# Top_Sheet.net
KiCad netlist of a schematic drawn in Altium Designer
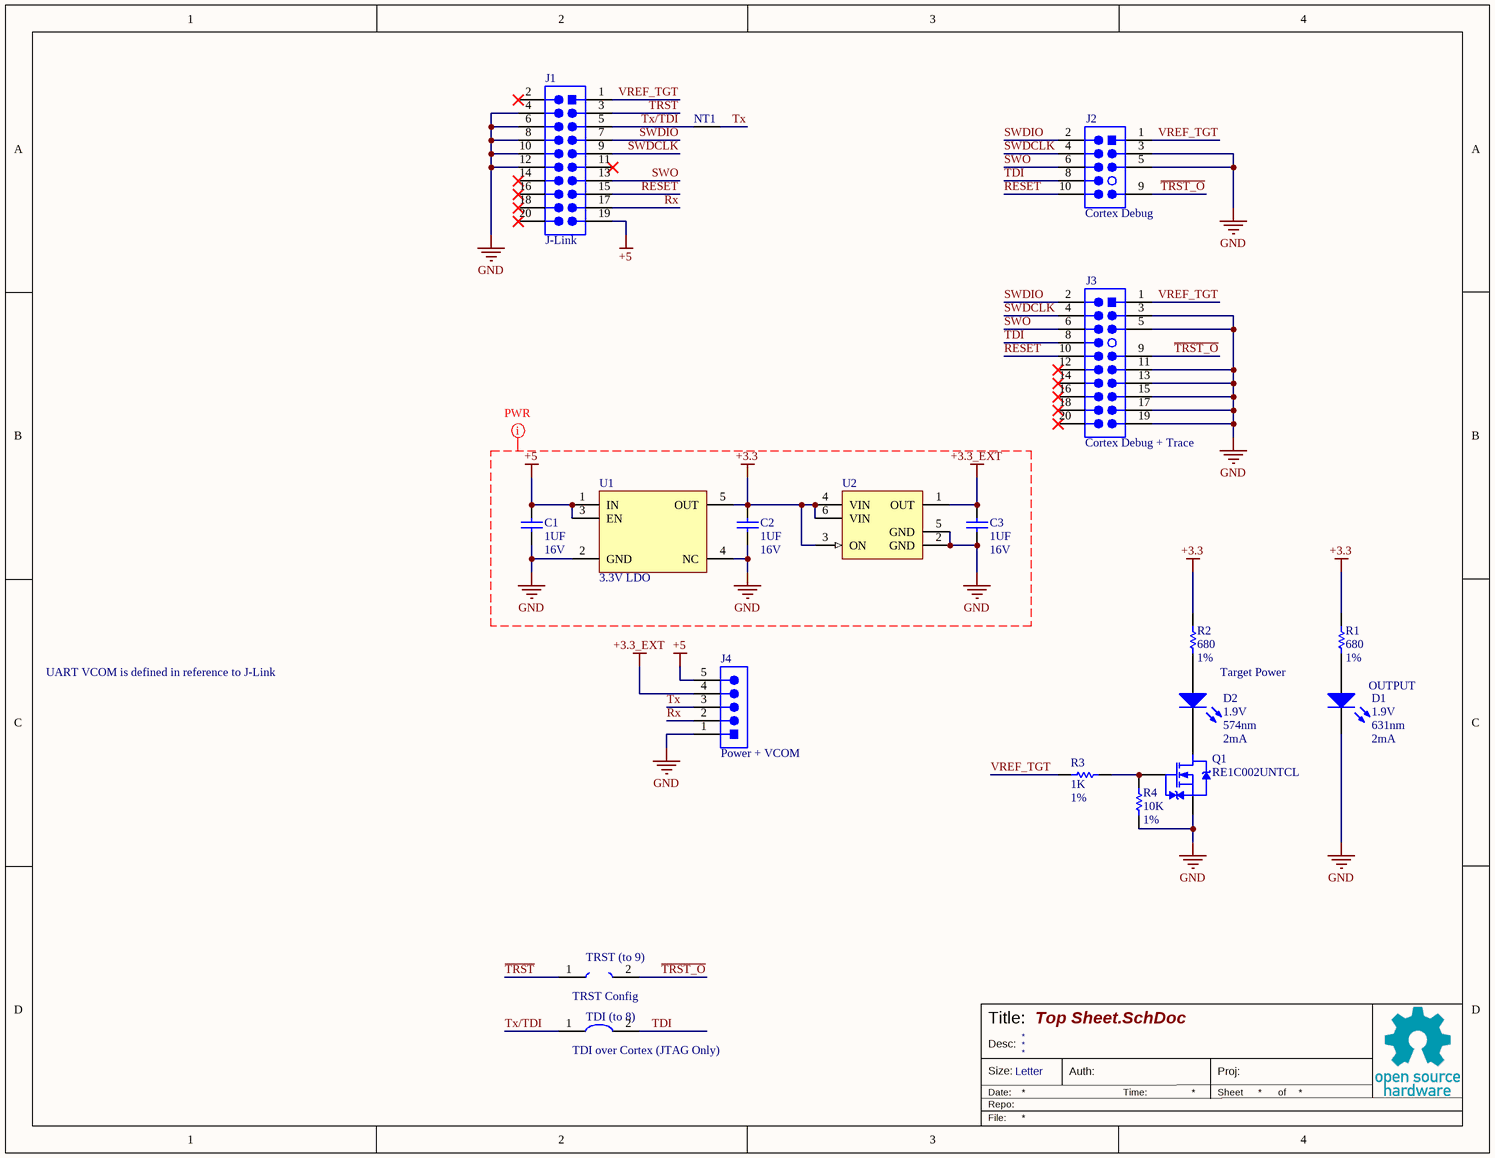
[diagram p0: Top Sheet.SchDoc]

(export (version "E")
  (design (tool "Eeschema 10.0.6"))
  (components
    (comp (ref "C1")
      (value "CAP 0603 1UF 16V 10% X7R")
      (footprint "0603_CAP")
      (description "Capacitor Surface Mount 0603 Footprint 1UF 16V 10% Tolerance Ceramic X7R")
      (fields
        (field (name "VAL") "1UF")
        (field (name "VOL") "16V")
        (field (name "MANUFACTURER") "Various")
        (field (name "VOLTAGE") "16V")
      )
      (libsource (lib "Passive Components") (part "cap"))
    )
    (comp (ref "C2")
      (value "CAP 0603 1UF 16V 10% X7R")
      (footprint "0603_CAP")
      (description "Capacitor Surface Mount 0603 Footprint 1UF 16V 10% Tolerance Ceramic X7R")
      (fields
        (field (name "VAL") "1UF")
        (field (name "VOL") "16V")
        (field (name "MANUFACTURER") "Various")
        (field (name "VOLTAGE") "16V")
      )
      (libsource (lib "Passive Components") (part "cap"))
    )
    (comp (ref "C3")
      (value "CAP 0603 1UF 16V 10% X7R")
      (footprint "0603_CAP")
      (description "Capacitor Surface Mount 0603 Footprint 1UF 16V 10% Tolerance Ceramic X7R")
      (fields
        (field (name "VAL") "1UF")
        (field (name "VOL") "16V")
        (field (name "MANUFACTURER") "Various")
        (field (name "VOLTAGE") "16V")
      )
      (libsource (lib "Passive Components") (part "cap"))
    )
    (comp (ref "D1")
      (value "Red LED")
      (footprint "SM0805HCL")
      (description "Red 631nm LED Indication - Discrete 1.9V 0805 (2012 Metric)")
      (fields
        (field (name "MANUFACTURER") "Bivar")
        (field (name "VOLTAGE RATING") "1.9V")
        (field (name "WAVELENGTH") "631nm")
        (field (name "TEST CURRENT") "2mA")
      )
      (libsource (lib "Discrete Semiconductors") (part "LED_Single"))
    )
    (comp (ref "D2")
      (value "Green LED")
      (footprint "SM0805GCL")
      (description "Green 574nm LED Indication - Discrete 1.9V 0805 (2012 Metric)")
      (fields
        (field (name "MANUFACTURER") "Bivar")
        (field (name "VOLTAGE RATING") "1.9V")
        (field (name "WAVELENGTH") "574nm")
        (field (name "TEST CURRENT") "2mA")
      )
      (libsource (lib "Discrete Semiconductors") (part "LED_Single"))
    )
    (comp (ref "J1")
      (value "20 contact Female header, RA")
      (footprint "SFH11-PBPC-D10-RA-BK")
      (description "20 Position Header Connector  Through Hole, Right Angle")
      (fields (field (name "MANUFACTURER") "Sullins"))
      (libsource (lib "Connectors") (part "Header 10X2"))
    )
    (comp (ref "J2")
      (value "Cortex Debug, 0.050\" 10 Pin")
      (footprint "FTSH-105-01-F-DV-007-K PLUGOUT")
      (description "10 Pin Shrouded Header, 0.050\", Key Pin 7")
      (fields (field (name "MANUFACTURER") "Samtech"))
      (libsource (lib "Connectors") (part "Cortex Debug"))
    )
    (comp (ref "J3")
      (value "Cortex Debug+ETM Connector, 0.050\" 20 Pin")
      (footprint "FTSH-110-01-F-DV-007-K plugout")
      (description "20 Pin Shrouded Header, 0.050\", Key Pin 7")
      (fields (field (name "MANUFACTURER") "Samtech"))
      (libsource (lib "Connectors") (part "Cortex Trace"))
    )
    (comp (ref "J4")
      (value "5 Pin, 2mm")
      (footprint "B5B-PH-K-S with wires")
      (description "JST 5-Pin PH Series, THT (2MM, 5 Pos)")
      (fields (field (name "MANUFACTURER") "J.S.T. Mfg. Co.,Ltd"))
      (libsource (lib "Connectors") (part "Header 1X5"))
    )
    (comp (ref "NT1")
      (value "Net Tie")
      (footprint "NT10")
      (description "Generic Net Tie")
      (libsource (lib "Hardware") (part "TIE"))
    )
    (comp (ref "Q1")
      (value "N-Channel MOSFET")
      (footprint "SC89")
      (description "N-Channel 20V 200mA (Ta) 150mW (Ta) Surface Mount EMT3F (SOT-416FL)")
      (fields
        (field (name "MANUFACTURER") "Rohm Semiconductor")
        (field (name "MANUFACTURER P/N") "RE1C002UNTCL")
      )
      (libsource (lib "Discrete Semiconductors") (part "N_Channel_SC89_ESD"))
    )
    (comp (ref "R1")
      (value "RES 0603 680 1%")
      (footprint "0603_RES")
      (description "Resistor Surface Mount, 680 Ohms, 0603 Footprint, 1% Tolerance 0.1W")
      (fields
        (field (name "VAL") "680")
        (field (name "TOL") "1%")
        (field (name "MANUFACTURER") "Various")
        (field (name "TOLERANCE") "1%")
      )
      (libsource (lib "Passive Components") (part "res"))
    )
    (comp (ref "R2")
      (value "RES 0603 680 1%")
      (footprint "0603_RES")
      (description "Resistor Surface Mount, 680 Ohms, 0603 Footprint, 1% Tolerance 0.1W")
      (fields
        (field (name "VAL") "680")
        (field (name "TOL") "1%")
        (field (name "MANUFACTURER") "Various")
        (field (name "TOLERANCE") "1%")
      )
      (libsource (lib "Passive Components") (part "res"))
    )
    (comp (ref "R3")
      (value "RES 0603 1K 1%")
      (footprint "0603_RES")
      (description "Resistor Surface Mount, 1K Ohms, 0603 Footprint, 1% Tolerance 0.1W")
      (fields
        (field (name "VAL") "1K")
        (field (name "TOL") "1%")
        (field (name "MANUFACTURER") "Various")
        (field (name "TOLERANCE") "1%")
      )
      (libsource (lib "Passive Components") (part "res"))
    )
    (comp (ref "R4")
      (value "RES 0603 10K 1%")
      (footprint "0603_RES")
      (description "Resistor Surface Mount, 10K Ohms, 0603 Footprint, 1% Tolerance 0.1W")
      (fields
        (field (name "VAL") "10K")
        (field (name "TOL") "1%")
        (field (name "MANUFACTURER") "Various")
        (field (name "TOLERANCE") "1%")
      )
      (libsource (lib "Passive Components") (part "res"))
    )
    (comp (ref "TDI (to 8)")
      (value "SMD JMP")
      (footprint "SMD_JMP_SHRT")
      (description "SMD Jumper, Shorted")
      (libsource (lib "Hardware") (part "jmp-link-nobom"))
    )
    (comp (ref "TRST (to 9)")
      (value "SMD JMP")
      (footprint "SMD_JMP_OPEN")
      (description "SMD Jumper, Open")
      (libsource (lib "Hardware") (part "jmp-link-open"))
    )
    (comp (ref "U1")
      (value "3.3V LDO")
      (footprint "SOT23-5")
      (description "Linear Voltage Regulator IC  1 Output  500mA SOT-23-5")
      (fields (field (name "MANUFACTURER") "Texas Insturments"))
      (libsource (lib "Integrated Circuits") (part "TLV755P"))
    )
    (comp (ref "U2")
      (value "Hot Swap Controller")
      (footprint "TI_DBV0006A")
      (description "Power Switch/Driver 1:1 P-Channel 1.8A SOT-23-6")
      (fields (field (name "MANUFACTURER") "Texas Instruments"))
      (libsource (lib "Integrated Circuits") (part "TPS22929D"))
    )
  )
  (nets
    (net (code "1") (name "+3.3") (class "Default")
      (node (ref "C2") (pin "2") (pinfunction "2_2") (pintype "passive"))
      (node (ref "R1") (pin "2") (pinfunction "2_2") (pintype "passive"))
      (node (ref "R2") (pin "2") (pinfunction "2_2") (pintype "passive"))
      (node (ref "U1") (pin "5") (pinfunction "OUT_5") (pintype "power_in"))
      (node (ref "U2") (pin "3") (pinfunction "ON_3") (pintype "input"))
      (node (ref "U2") (pin "4") (pinfunction "VIN_4") (pintype "power_in"))
      (node (ref "U2") (pin "6") (pinfunction "VIN_6") (pintype "power_in"))
    )
    (net (code "2") (name "+3.3_EXT") (class "Default")
      (node (ref "C3") (pin "2") (pinfunction "2_2") (pintype "passive"))
      (node (ref "J4") (pin "4") (pinfunction "4_4") (pintype "passive"))
      (node (ref "U2") (pin "1") (pinfunction "OUT_1") (pintype "power_in"))
    )
    (net (code "3") (name "+5") (class "Default")
      (node (ref "C1") (pin "2") (pinfunction "2_2") (pintype "passive"))
      (node (ref "J1") (pin "19") (pinfunction "19_19") (pintype "passive"))
      (node (ref "J4") (pin "5") (pinfunction "5_5") (pintype "passive"))
      (node (ref "U1") (pin "1") (pinfunction "IN_1") (pintype "power_in"))
      (node (ref "U1") (pin "3") (pinfunction "EN_3") (pintype "passive"))
    )
    (net (code "4") (name "/RESET") (class "Default")
      (node (ref "J1") (pin "15") (pinfunction "15_15") (pintype "passive"))
      (node (ref "J2") (pin "10") (pinfunction "RESET_10") (pintype "passive"))
      (node (ref "J3") (pin "10") (pinfunction "RESET_10") (pintype "passive"))
    )
    (net (code "5") (name "/Rx") (class "Default")
      (node (ref "J1") (pin "17") (pinfunction "17_17") (pintype "passive"))
      (node (ref "J4") (pin "2") (pinfunction "2_2") (pintype "passive"))
    )
    (net (code "6") (name "/SWDCLK") (class "Default")
      (node (ref "J1") (pin "9") (pinfunction "9_9") (pintype "passive"))
      (node (ref "J2") (pin "4") (pinfunction "SWDCLK/TCK_4") (pintype "passive"))
      (node (ref "J3") (pin "4") (pinfunction "SWDCLK/TCK_4") (pintype "passive"))
    )
    (net (code "7") (name "/SWDIO") (class "Default")
      (node (ref "J1") (pin "7") (pinfunction "7_7") (pintype "passive"))
      (node (ref "J2") (pin "2") (pinfunction "SWDIO/TMS_2") (pintype "passive"))
      (node (ref "J3") (pin "2") (pinfunction "SWDIO/TMS_2") (pintype "passive"))
    )
    (net (code "8") (name "/SWO") (class "Default")
      (node (ref "J1") (pin "13") (pinfunction "13_13") (pintype "passive"))
      (node (ref "J2") (pin "6") (pinfunction "SWO/TDO_6") (pintype "passive"))
      (node (ref "J3") (pin "6") (pinfunction "SWO/TDO/EXTa/TRACECTL_6") (pintype "passive"))
    )
    (net (code "9") (name "/TDI") (class "Default")
      (node (ref "J2") (pin "8") (pinfunction "NC/TDI_8") (pintype "passive"))
      (node (ref "J3") (pin "8") (pinfunction "NC/EXTb/TDI_8") (pintype "passive"))
      (node (ref "TDI (to 8)") (pin "2") (pinfunction "2_2") (pintype "passive"))
    )
    (net (code "10") (name "/TRST") (class "Default")
      (node (ref "J1") (pin "3") (pinfunction "3_3") (pintype "passive"))
      (node (ref "TRST (to 9)") (pin "1") (pinfunction "1_1") (pintype "passive"))
    )
    (net (code "11") (name "/TRST_O") (class "Default")
      (node (ref "J2") (pin "9") (pinfunction "GNDDetect_9") (pintype "power_in"))
      (node (ref "J3") (pin "9") (pinfunction "GNDDetect_9") (pintype "power_in"))
      (node (ref "TRST (to 9)") (pin "2") (pinfunction "2_2") (pintype "passive"))
    )
    (net (code "12") (name "/Tx") (class "Default")
      (node (ref "J4") (pin "3") (pinfunction "3_3") (pintype "passive"))
      (node (ref "NT1") (pin "2") (pinfunction "2_2") (pintype "passive"))
    )
    (net (code "13") (name "/Tx{slash}TDI") (class "Default")
      (node (ref "J1") (pin "5") (pinfunction "5_5") (pintype "passive"))
      (node (ref "NT1") (pin "1") (pinfunction "1_1") (pintype "passive"))
      (node (ref "TDI (to 8)") (pin "1") (pinfunction "1_1") (pintype "passive"))
    )
    (net (code "14") (name "/VREF_TGT") (class "Default")
      (node (ref "J1") (pin "1") (pinfunction "1_1") (pintype "passive"))
      (node (ref "J2") (pin "1") (pinfunction "VCC_1") (pintype "power_in"))
      (node (ref "J3") (pin "1") (pinfunction "VCC_1") (pintype "power_in"))
      (node (ref "R3") (pin "1") (pinfunction "1_1") (pintype "passive"))
    )
    (net (code "15") (name "GND") (class "Default")
      (node (ref "C1") (pin "1") (pinfunction "1_1") (pintype "passive"))
      (node (ref "C2") (pin "1") (pinfunction "1_1") (pintype "passive"))
      (node (ref "C3") (pin "1") (pinfunction "1_1") (pintype "passive"))
      (node (ref "D1") (pin "K") (pinfunction "K_K") (pintype "passive"))
      (node (ref "J1") (pin "10") (pinfunction "10_10") (pintype "passive"))
      (node (ref "J1") (pin "12") (pinfunction "12_12") (pintype "passive"))
      (node (ref "J1") (pin "4") (pinfunction "4_4") (pintype "passive"))
      (node (ref "J1") (pin "6") (pinfunction "6_6") (pintype "passive"))
      (node (ref "J1") (pin "8") (pinfunction "8_8") (pintype "passive"))
      (node (ref "J2") (pin "3") (pinfunction "GND_3") (pintype "power_in"))
      (node (ref "J2") (pin "5") (pinfunction "GND_5") (pintype "power_in"))
      (node (ref "J3") (pin "11") (pinfunction "GND/TgtPwr+Cap_11") (pintype "passive"))
      (node (ref "J3") (pin "13") (pinfunction "13_13") (pintype "power_in"))
      (node (ref "J3") (pin "15") (pinfunction "GND_15") (pintype "power_in"))
      (node (ref "J3") (pin "17") (pinfunction "GND_17") (pintype "power_in"))
      (node (ref "J3") (pin "19") (pinfunction "GND_19") (pintype "power_in"))
      (node (ref "J3") (pin "3") (pinfunction "GND_3") (pintype "power_in"))
      (node (ref "J3") (pin "5") (pinfunction "GND_5") (pintype "power_in"))
      (node (ref "J4") (pin "1") (pinfunction "1_1") (pintype "passive"))
      (node (ref "Q1") (pin "2") (pinfunction "S_2") (pintype "passive"))
      (node (ref "R4") (pin "1") (pinfunction "1_1") (pintype "passive"))
      (node (ref "U1") (pin "2") (pinfunction "GND_2") (pintype "power_in"))
      (node (ref "U1") (pin "4") (pinfunction "NC_4") (pintype "passive"))
      (node (ref "U2") (pin "2") (pinfunction "GND_2") (pintype "power_in"))
      (node (ref "U2") (pin "5") (pinfunction "GND_5") (pintype "power_in"))
    )
    (net (code "16") (name "Net-(D1-PadA)") (class "Default")
      (node (ref "D1") (pin "A") (pinfunction "A_A") (pintype "passive"))
      (node (ref "R1") (pin "1") (pinfunction "1_1") (pintype "passive"))
    )
    (net (code "17") (name "Net-(D2-PadA)") (class "Default")
      (node (ref "D2") (pin "A") (pinfunction "A_A") (pintype "passive"))
      (node (ref "R2") (pin "1") (pinfunction "1_1") (pintype "passive"))
    )
    (net (code "18") (name "Net-(Q1-D)") (class "Default")
      (node (ref "D2") (pin "K") (pinfunction "K_K") (pintype "passive"))
      (node (ref "Q1") (pin "3") (pinfunction "D_3") (pintype "passive"))
    )
    (net (code "19") (name "Net-(Q1-G)") (class "Default")
      (node (ref "Q1") (pin "1") (pinfunction "G_1") (pintype "passive"))
      (node (ref "R3") (pin "2") (pinfunction "2_2") (pintype "passive"))
      (node (ref "R4") (pin "2") (pinfunction "2_2") (pintype "passive"))
    )
    (net (code "20") (name "unconnected-(J1-Pad2)") (class "Default")
      (node (ref "J1") (pin "2") (pinfunction "2_2") (pintype "passive+no_connect"))
    )
    (net (code "21") (name "unconnected-(J1-Pad11)") (class "Default")
      (node (ref "J1") (pin "11") (pinfunction "11_11") (pintype "passive+no_connect"))
    )
    (net (code "22") (name "unconnected-(J1-Pad14)") (class "Default")
      (node (ref "J1") (pin "14") (pinfunction "14_14") (pintype "passive+no_connect"))
    )
    (net (code "23") (name "unconnected-(J1-Pad16)") (class "Default")
      (node (ref "J1") (pin "16") (pinfunction "16_16") (pintype "passive+no_connect"))
    )
    (net (code "24") (name "unconnected-(J1-Pad18)") (class "Default")
      (node (ref "J1") (pin "18") (pinfunction "18_18") (pintype "passive+no_connect"))
    )
    (net (code "25") (name "unconnected-(J1-Pad20)") (class "Default")
      (node (ref "J1") (pin "20") (pinfunction "20_20") (pintype "passive+no_connect"))
    )
    (net (code "26") (name "unconnected-(J3-TRACECLK-Pad12)") (class "Default")
      (node (ref "J3") (pin "12") (pinfunction "TRACECLK_12") (pintype "passive+no_connect"))
    )
    (net (code "27") (name "unconnected-(J3-TRACEDATA[0]-Pad14)") (class "Default")
      (node (ref "J3") (pin "14") (pinfunction "TRACEDATA[0]_14") (pintype "passive+no_connect"))
    )
    (net (code "28") (name "unconnected-(J3-TRACEDATA[1]-Pad16)") (class "Default")
      (node (ref "J3") (pin "16") (pinfunction "TRACEDATA[1]_16") (pintype "passive+no_connect"))
    )
    (net (code "29") (name "unconnected-(J3-TRACEDATA[2]-Pad18)") (class "Default")
      (node (ref "J3") (pin "18") (pinfunction "TRACEDATA[2]_18") (pintype "passive+no_connect"))
    )
    (net (code "30") (name "unconnected-(J3-TRACEDATA[3]-Pad20)") (class "Default")
      (node (ref "J3") (pin "20") (pinfunction "TRACEDATA[3]_20") (pintype "passive+no_connect"))
    )
  )
)
